# Power.net
KiCad netlist of a schematic drawn in Altium Designer
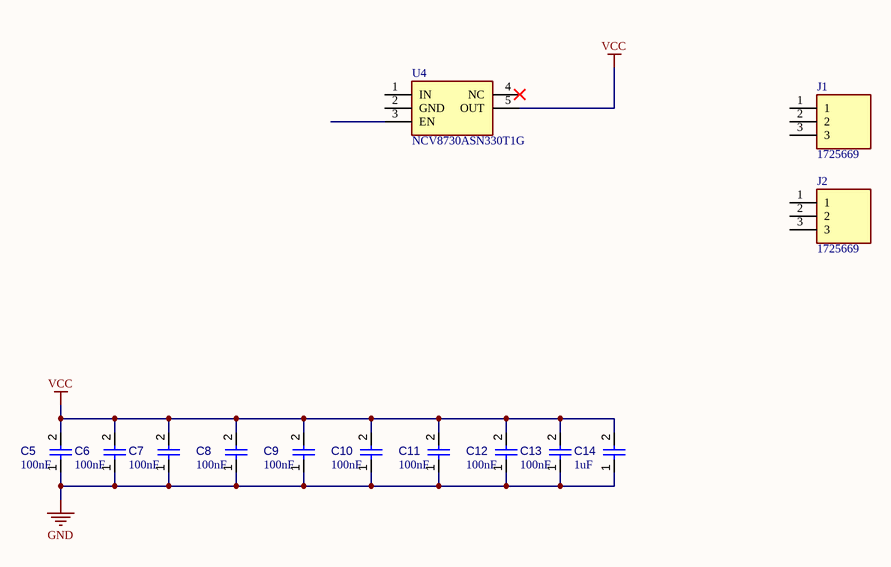
[diagram p0: Power.SchDoc]

(export (version "E")
  (design (tool "Eeschema 10.0.6"))
  (components
    (comp (ref "C5")
      (value "100nF")
      (footprint "CAPC0603(1608)100_L")
      (description "Capacitor")
      (fields (field (name "Comment") "Capacitors,0603,smt,100nF"))
      (libsource (lib "Riley Peterson") (part "CAP-NP-2"))
    )
    (comp (ref "C6")
      (value "100nF")
      (footprint "CAPC0603(1608)100_L")
      (description "Capacitor")
      (fields (field (name "Comment") "Capacitors,0603,smt,100nF"))
      (libsource (lib "Riley Peterson") (part "CAP-NP-2"))
    )
    (comp (ref "C7")
      (value "100nF")
      (footprint "CAPC0603(1608)100_L")
      (description "Capacitor")
      (fields (field (name "Comment") "Capacitors,0603,smt,100nF"))
      (libsource (lib "Riley Peterson") (part "CAP-NP-2"))
    )
    (comp (ref "C8")
      (value "100nF")
      (footprint "CAPC0603(1608)100_L")
      (description "Capacitor")
      (fields (field (name "Comment") "Capacitors,0603,smt,100nF"))
      (libsource (lib "Riley Peterson") (part "CAP-NP-2"))
    )
    (comp (ref "C9")
      (value "100nF")
      (footprint "CAPC0603(1608)100_L")
      (description "Capacitor")
      (fields (field (name "Comment") "Capacitors,0603,smt,100nF"))
      (libsource (lib "Riley Peterson") (part "CAP-NP-2"))
    )
    (comp (ref "C10")
      (value "100nF")
      (footprint "CAPC0603(1608)100_L")
      (description "Capacitor")
      (fields (field (name "Comment") "Capacitors,0603,smt,100nF"))
      (libsource (lib "Riley Peterson") (part "CAP-NP-2"))
    )
    (comp (ref "C11")
      (value "100nF")
      (footprint "CAPC0603(1608)100_L")
      (description "Capacitor")
      (fields (field (name "Comment") "Capacitors,0603,smt,100nF"))
      (libsource (lib "Riley Peterson") (part "CAP-NP-2"))
    )
    (comp (ref "C12")
      (value "100nF")
      (footprint "CAPC0603(1608)100_L")
      (description "Capacitor")
      (fields (field (name "Comment") "Capacitors,0603,smt,100nF"))
      (libsource (lib "Riley Peterson") (part "CAP-NP-2"))
    )
    (comp (ref "C13")
      (value "100nF")
      (footprint "CAPC0603(1608)100_L")
      (description "Capacitor")
      (fields (field (name "Comment") "Capacitors,0603,smt,100nF"))
      (libsource (lib "Riley Peterson") (part "CAP-NP-2"))
    )
    (comp (ref "C14")
      (value "1uF")
      (footprint "CAPC0603(1608)100_L")
      (description "Capacitor")
      (fields (field (name "Comment") "Capacitors,0603,smt,1uF"))
      (libsource (lib "Riley Peterson") (part "CAP-NP-2"))
    )
    (comp (ref "J1")
      (value "1725669")
      (footprint "SamacSys:1725669")
      (description "Connector")
      (fields (field (name "MOUSER PART NUMBER") "651-1725669"))
      (libsource (lib "*") (part "1725669"))
    )
    (comp (ref "J2")
      (value "1725669")
      (footprint "SamacSys:1725669")
      (description "Connector")
      (fields (field (name "MOUSER PART NUMBER") "651-1725669"))
      (libsource (lib "*") (part "1725669"))
    )
    (comp (ref "U4")
      (value "NCV8730ASN330T1G")
      (footprint "SamacSys:SOT95P275X110-5N")
      (description "Integrated Circuit")
      (fields (field (name "MOUSER PART NUMBER") "863-NCV8730ASN330T1G"))
      (libsource (lib "*") (part "NCV8730ASN330T1G"))
    )
  )
  (nets
    (net (code "1") (name "GND") (class "Default")
      (node (ref "C10") (pin "1") (pinfunction "1_1") (pintype "passive"))
      (node (ref "C11") (pin "1") (pinfunction "1_1") (pintype "passive"))
      (node (ref "C12") (pin "1") (pinfunction "1_1") (pintype "passive"))
      (node (ref "C13") (pin "1") (pinfunction "1_1") (pintype "passive"))
      (node (ref "C14") (pin "1") (pinfunction "1_1") (pintype "passive"))
      (node (ref "C5") (pin "1") (pinfunction "1_1") (pintype "passive"))
      (node (ref "C6") (pin "1") (pinfunction "1_1") (pintype "passive"))
      (node (ref "C7") (pin "1") (pinfunction "1_1") (pintype "passive"))
      (node (ref "C8") (pin "1") (pinfunction "1_1") (pintype "passive"))
      (node (ref "C9") (pin "1") (pinfunction "1_1") (pintype "passive"))
    )
    (net (code "2") (name "VCC") (class "Default")
      (node (ref "C10") (pin "2") (pinfunction "2_2") (pintype "passive"))
      (node (ref "C11") (pin "2") (pinfunction "2_2") (pintype "passive"))
      (node (ref "C12") (pin "2") (pinfunction "2_2") (pintype "passive"))
      (node (ref "C13") (pin "2") (pinfunction "2_2") (pintype "passive"))
      (node (ref "C14") (pin "2") (pinfunction "2_2") (pintype "passive"))
      (node (ref "C5") (pin "2") (pinfunction "2_2") (pintype "passive"))
      (node (ref "C6") (pin "2") (pinfunction "2_2") (pintype "passive"))
      (node (ref "C7") (pin "2") (pinfunction "2_2") (pintype "passive"))
      (node (ref "C8") (pin "2") (pinfunction "2_2") (pintype "passive"))
      (node (ref "C9") (pin "2") (pinfunction "2_2") (pintype "passive"))
      (node (ref "U4") (pin "5") (pinfunction "OUT_5") (pintype "passive"))
    )
    (net (code "3") (name "unconnected-(J1-Pad1)") (class "Default")
      (node (ref "J1") (pin "1") (pinfunction "1_1") (pintype "passive"))
    )
    (net (code "4") (name "unconnected-(J1-Pad2)") (class "Default")
      (node (ref "J1") (pin "2") (pinfunction "2_2") (pintype "passive"))
    )
    (net (code "5") (name "unconnected-(J1-Pad3)") (class "Default")
      (node (ref "J1") (pin "3") (pinfunction "3_3") (pintype "passive"))
    )
    (net (code "6") (name "unconnected-(J2-Pad1)") (class "Default")
      (node (ref "J2") (pin "1") (pinfunction "1_1") (pintype "passive"))
    )
    (net (code "7") (name "unconnected-(J2-Pad2)") (class "Default")
      (node (ref "J2") (pin "2") (pinfunction "2_2") (pintype "passive"))
    )
    (net (code "8") (name "unconnected-(J2-Pad3)") (class "Default")
      (node (ref "J2") (pin "3") (pinfunction "3_3") (pintype "passive"))
    )
    (net (code "9") (name "unconnected-(U4-EN-Pad3)") (class "Default")
      (node (ref "U4") (pin "3") (pinfunction "EN_3") (pintype "passive"))
    )
    (net (code "10") (name "unconnected-(U4-GND-Pad2)") (class "Default")
      (node (ref "U4") (pin "2") (pinfunction "GND_2") (pintype "passive"))
    )
    (net (code "11") (name "unconnected-(U4-IN-Pad1)") (class "Default")
      (node (ref "U4") (pin "1") (pinfunction "IN_1") (pintype "passive"))
    )
    (net (code "12") (name "unconnected-(U4-NC-Pad4)") (class "Default")
      (node (ref "U4") (pin "4") (pinfunction "NC_4") (pintype "passive+no_connect"))
    )
  )
)
